# SCH_fig2_2021-11-24.net
KiCad netlist of a schematic drawn in EasyEDA
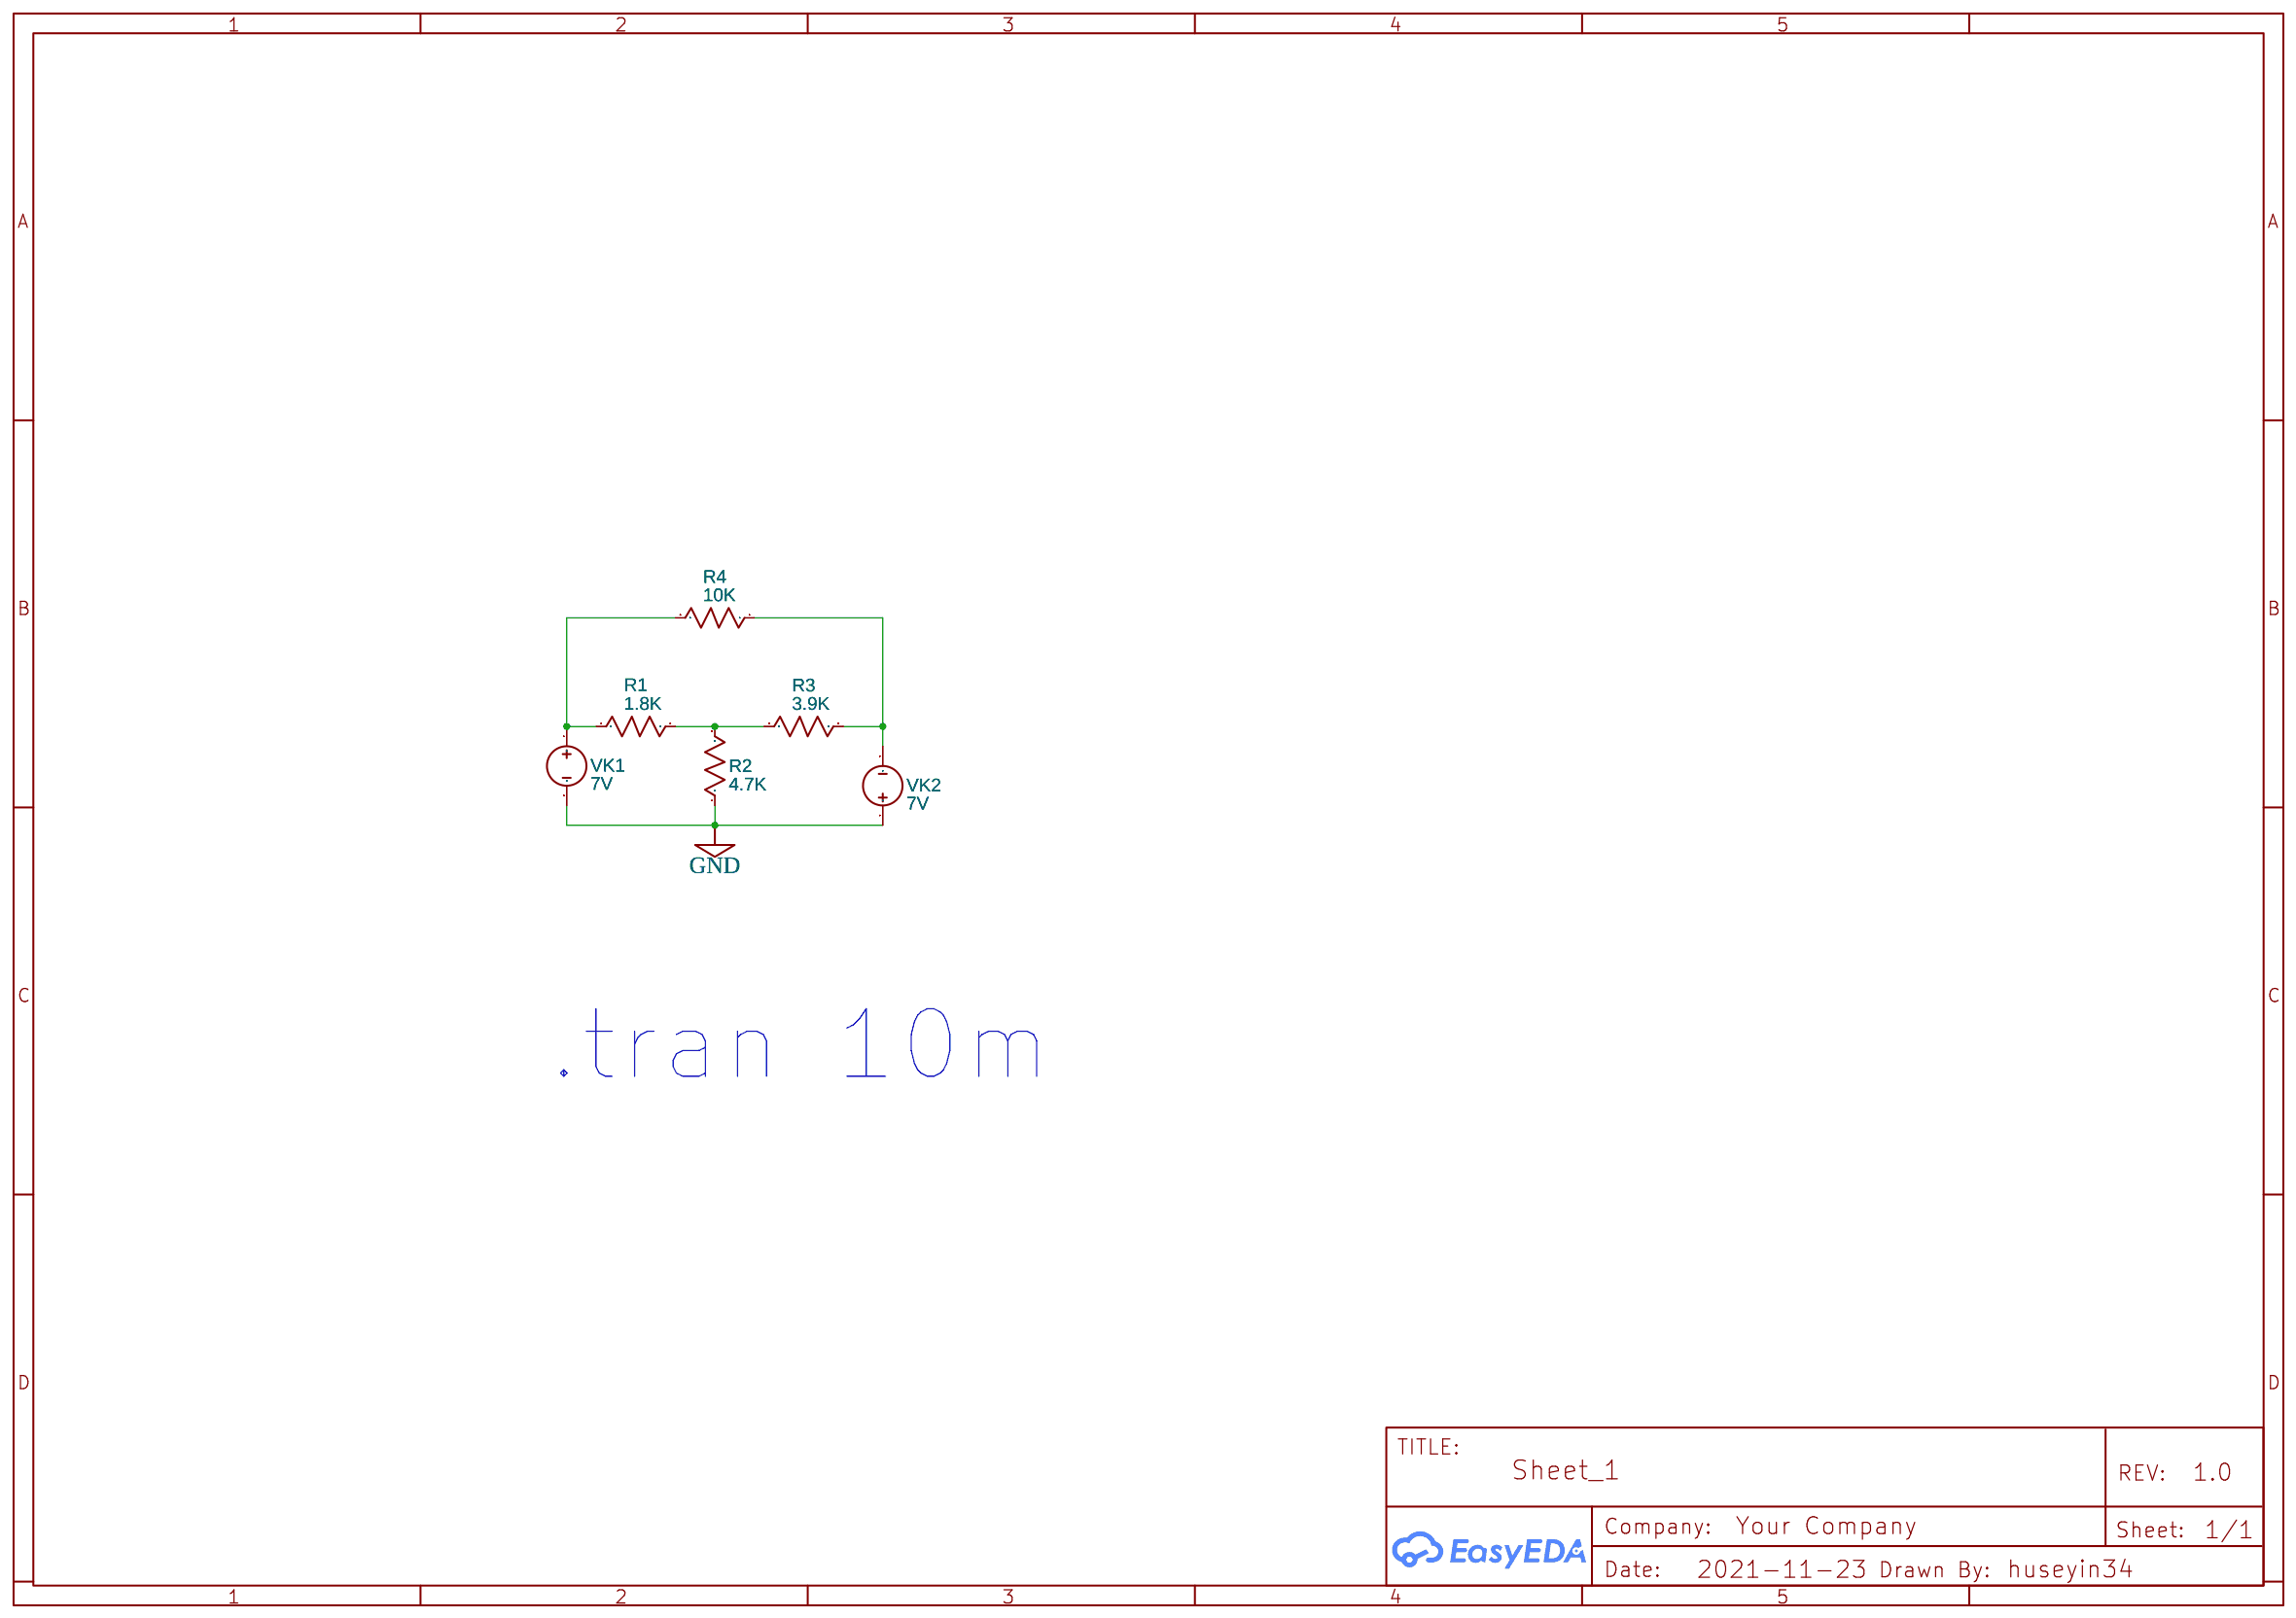
[diagram p0: schematic sheet]

(export (version "E")
  (design (tool "Eeschema 10.0.6"))
  (components
    (comp (ref "R1") (value "1.8K") (libsource (lib "") (part "Resistor_US_2")))
    (comp (ref "R2") (value "4.7K") (libsource (lib "") (part "Resistor_US")))
    (comp (ref "R3") (value "3.9K") (libsource (lib "") (part "Resistor_US_1")))
    (comp (ref "R4") (value "10K") (libsource (lib "") (part "Resistor_US_1")))
    (comp (ref "VK1") (value "7V") (libsource (lib "") (part "VDC_1")))
    (comp (ref "VK2") (value "7V") (libsource (lib "") (part "VDC")))
  )
  (nets
    (net (code "1") (name "GND") (class "Default")
      (node (ref "R2") (pin "1") (pinfunction "1_1") (pintype "unspecified"))
      (node (ref "VK1") (pin "2") (pinfunction "2_2") (pintype "unspecified"))
      (node (ref "VK2") (pin "1") (pinfunction "1_1") (pintype "unspecified"))
    )
    (net (code "2") (name "Net-(R1-Pad1)") (class "Default")
      (node (ref "R1") (pin "1") (pinfunction "1_1") (pintype "unspecified"))
      (node (ref "R4") (pin "2") (pinfunction "2_2") (pintype "unspecified"))
      (node (ref "VK1") (pin "1") (pinfunction "1_1") (pintype "unspecified"))
    )
    (net (code "3") (name "Net-(R1-Pad2)") (class "Default")
      (node (ref "R1") (pin "2") (pinfunction "2_2") (pintype "unspecified"))
      (node (ref "R2") (pin "2") (pinfunction "2_2") (pintype "unspecified"))
      (node (ref "R3") (pin "2") (pinfunction "2_2") (pintype "unspecified"))
    )
    (net (code "4") (name "Net-(R3-Pad1)") (class "Default")
      (node (ref "R3") (pin "1") (pinfunction "1_1") (pintype "unspecified"))
      (node (ref "R4") (pin "1") (pinfunction "1_1") (pintype "unspecified"))
      (node (ref "VK2") (pin "2") (pinfunction "2_2") (pintype "unspecified"))
    )
  )
)
